# Battery_tester.net
KiCad netlist of a schematic drawn in EAGLE
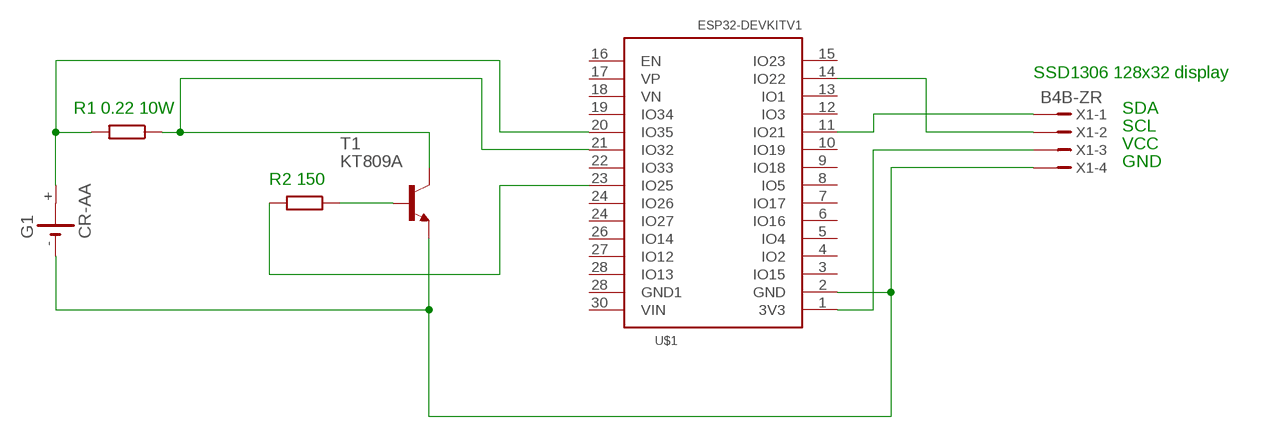
[diagram p0: schematic, sheet 1]

(export (version "E")
  (design (tool "Eeschema 10.0.6"))
  (components
    (comp (ref "G1")
      (value "CR-AA")
      (footprint "eagle-import:CRAA")
      (libsource (lib "eagle-import") (part "CR-AA"))
    )
    (comp (ref "T1")
      (value "KT809A")
      (footprint "eagle-import:TO3")
      (libsource (lib "eagle-import") (part "-NPN-TO3/"))
    )
    (comp (ref "U$1")
      (value "ESP32DEVKITV1")
      (footprint "eagle-import:ESP32-DEVKITV1")
      (libsource (lib "eagle-import") (part "ESP32DEVKITV1"))
    )
    (comp (ref "X1")
      (value "B4B-ZR")
      (footprint "eagle-import:B4B-ZR")
      (fields (field (name "MF") "FARNELL") (field (name "MPN") "B4B-ZR(LF)(SN)"))
      (libsource (lib "eagle-import") (part "?4B-ZRB"))
    )
  )
  (nets
    (net (code "1") (name "Net-(U$1-3V3)") (class "Default")
      (node (ref "U$1") (pin "1") (pinfunction "3V3_1") (pintype "bidirectional"))
      (node (ref "X1") (pin "3") (pinfunction "1_3") (pintype "passive"))
    )
    (net (code "2") (name "Net-(U$1-GND)") (class "Default")
      (node (ref "G1") (pin "-") (pinfunction "-_-") (pintype "passive"))
      (node (ref "T1") (pin "E") (pinfunction "E_E") (pintype "passive"))
      (node (ref "U$1") (pin "2") (pinfunction "GND_2") (pintype "bidirectional"))
      (node (ref "X1") (pin "4") (pinfunction "1_4") (pintype "passive"))
    )
    (net (code "3") (name "Net-(U$1-IO21)") (class "Default")
      (node (ref "U$1") (pin "11") (pinfunction "IO21_11") (pintype "bidirectional"))
      (node (ref "X1") (pin "1") (pinfunction "1_1") (pintype "passive"))
    )
    (net (code "4") (name "Net-(U$1-IO22)") (class "Default")
      (node (ref "U$1") (pin "14") (pinfunction "IO22_14") (pintype "bidirectional"))
      (node (ref "X1") (pin "2") (pinfunction "1_2") (pintype "passive"))
    )
    (net (code "5") (name "Net-(U$1-IO32)") (class "Default")
      (node (ref "T1") (pin "C") (pinfunction "C_C") (pintype "passive"))
      (node (ref "U$1") (pin "21") (pinfunction "IO32_21") (pintype "bidirectional"))
    )
    (net (code "6") (name "Net-(U$1-IO35)") (class "Default")
      (node (ref "G1") (pin "+") (pinfunction "+_+") (pintype "passive"))
      (node (ref "U$1") (pin "20") (pinfunction "IO35_20") (pintype "bidirectional"))
    )
    (net (code "7") (name "unconnected-(G1-+-Pad+@1)") (class "Default")
      (node (ref "G1") (pin "+@1") (pinfunction "+_+@1") (pintype "passive"))
    )
    (net (code "8") (name "unconnected-(T1-PadB)") (class "Default")
      (node (ref "T1") (pin "B") (pinfunction "B_B") (pintype "passive"))
    )
    (net (code "9") (name "unconnected-(U$1-EN-Pad16)") (class "Default")
      (node (ref "U$1") (pin "16") (pinfunction "EN_16") (pintype "bidirectional"))
    )
    (net (code "10") (name "unconnected-(U$1-GND1-Pad28)") (class "Default")
      (node (ref "U$1") (pin "28") (pinfunction "GND1_28") (pintype "bidirectional"))
    )
    (net (code "11") (name "unconnected-(U$1-IO1-Pad13)") (class "Default")
      (node (ref "U$1") (pin "13") (pinfunction "IO1_13") (pintype "bidirectional"))
    )
    (net (code "12") (name "unconnected-(U$1-IO2-Pad4)") (class "Default")
      (node (ref "U$1") (pin "4") (pinfunction "IO2_4") (pintype "bidirectional"))
    )
    (net (code "13") (name "unconnected-(U$1-IO3-Pad12)") (class "Default")
      (node (ref "U$1") (pin "12") (pinfunction "IO3_12") (pintype "bidirectional"))
    )
    (net (code "14") (name "unconnected-(U$1-IO4-Pad5)") (class "Default")
      (node (ref "U$1") (pin "5") (pinfunction "IO4_5") (pintype "bidirectional"))
    )
    (net (code "15") (name "unconnected-(U$1-IO5-Pad8)") (class "Default")
      (node (ref "U$1") (pin "8") (pinfunction "IO5_8") (pintype "bidirectional"))
    )
    (net (code "16") (name "unconnected-(U$1-IO12-Pad27)") (class "Default")
      (node (ref "U$1") (pin "27") (pinfunction "IO12_27") (pintype "bidirectional"))
    )
    (net (code "17") (name "unconnected-(U$1-IO13-Pad28)") (class "Default")
      (node (ref "U$1") (pin "28") (pinfunction "IO13_28") (pintype "bidirectional"))
    )
    (net (code "18") (name "unconnected-(U$1-IO14-Pad26)") (class "Default")
      (node (ref "U$1") (pin "26") (pinfunction "IO14_26") (pintype "bidirectional"))
    )
    (net (code "19") (name "unconnected-(U$1-IO15-Pad3)") (class "Default")
      (node (ref "U$1") (pin "3") (pinfunction "IO15_3") (pintype "bidirectional"))
    )
    (net (code "20") (name "unconnected-(U$1-IO16-Pad6)") (class "Default")
      (node (ref "U$1") (pin "6") (pinfunction "IO16_6") (pintype "bidirectional"))
    )
    (net (code "21") (name "unconnected-(U$1-IO17-Pad7)") (class "Default")
      (node (ref "U$1") (pin "7") (pinfunction "IO17_7") (pintype "bidirectional"))
    )
    (net (code "22") (name "unconnected-(U$1-IO18-Pad9)") (class "Default")
      (node (ref "U$1") (pin "9") (pinfunction "IO18_9") (pintype "bidirectional"))
    )
    (net (code "23") (name "unconnected-(U$1-IO19-Pad10)") (class "Default")
      (node (ref "U$1") (pin "10") (pinfunction "IO19_10") (pintype "bidirectional"))
    )
    (net (code "24") (name "unconnected-(U$1-IO23-Pad15)") (class "Default")
      (node (ref "U$1") (pin "15") (pinfunction "IO23_15") (pintype "bidirectional"))
    )
    (net (code "25") (name "unconnected-(U$1-IO25-Pad23)") (class "Default")
      (node (ref "U$1") (pin "23") (pinfunction "IO25_23") (pintype "bidirectional"))
    )
    (net (code "26") (name "unconnected-(U$1-IO26-Pad24)") (class "Default")
      (node (ref "U$1") (pin "24") (pinfunction "IO26_24") (pintype "bidirectional"))
    )
    (net (code "27") (name "unconnected-(U$1-IO27-Pad24)") (class "Default")
      (node (ref "U$1") (pin "24") (pinfunction "IO27_24") (pintype "bidirectional"))
    )
    (net (code "28") (name "unconnected-(U$1-IO33-Pad22)") (class "Default")
      (node (ref "U$1") (pin "22") (pinfunction "IO33_22") (pintype "bidirectional"))
    )
    (net (code "29") (name "unconnected-(U$1-IO34-Pad19)") (class "Default")
      (node (ref "U$1") (pin "19") (pinfunction "IO34_19") (pintype "bidirectional"))
    )
    (net (code "30") (name "unconnected-(U$1-VIN-Pad30)") (class "Default")
      (node (ref "U$1") (pin "30") (pinfunction "VIN_30") (pintype "bidirectional"))
    )
    (net (code "31") (name "unconnected-(U$1-VN-Pad18)") (class "Default")
      (node (ref "U$1") (pin "18") (pinfunction "VN_18") (pintype "bidirectional"))
    )
    (net (code "32") (name "unconnected-(U$1-VP-Pad17)") (class "Default")
      (node (ref "U$1") (pin "17") (pinfunction "VP_17") (pintype "bidirectional"))
    )
  )
)
